# DCF77_transmitter2.net
KiCad netlist of a schematic drawn in EAGLE
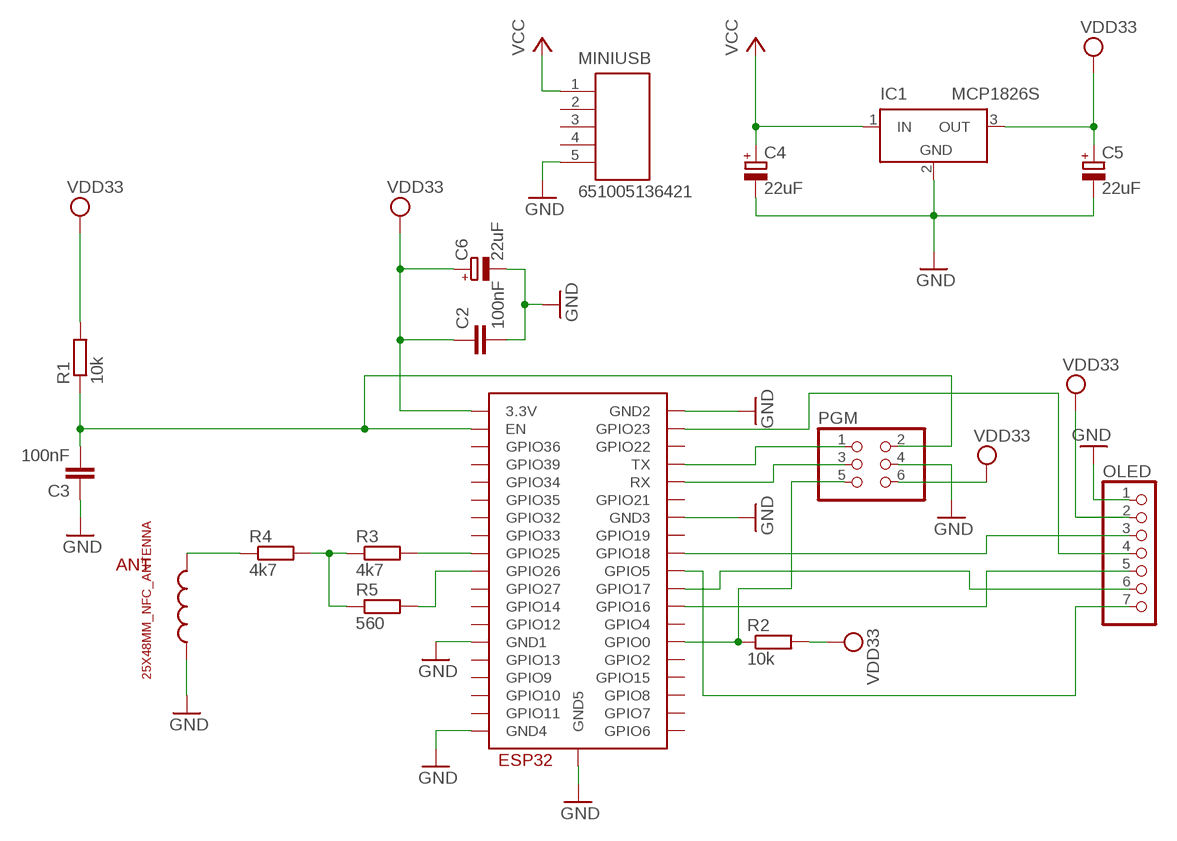
[diagram p0: schematic, sheet 1]

(export (version "E")
  (design (tool "Eeschema 10.0.6"))
  (components
    (comp (ref "ANT")
      (value "25X48MM_NFC_ANTENNA")
      (footprint "eagle-import:25X48MM_NFC_ANTENNA")
      (libsource (lib "eagle-import") (part "25X48MM_NFC_ANTENNA"))
    )
    (comp (ref "C2")
      (value "100nF")
      (footprint "eagle-import:C1206")
      (libsource (lib "eagle-import") (part "C-EUC1206"))
    )
    (comp (ref "C3")
      (value "100nF")
      (footprint "eagle-import:C1206")
      (libsource (lib "eagle-import") (part "C-EUC1206"))
    )
    (comp (ref "C4")
      (value "22uF")
      (footprint "eagle-import:B_3528-21W")
      (libsource (lib "eagle-import") (part "CPOL-EUB/3528-21W"))
    )
    (comp (ref "C5")
      (value "22uF")
      (footprint "eagle-import:B_3528-21W")
      (libsource (lib "eagle-import") (part "CPOL-EUB/3528-21W"))
    )
    (comp (ref "C6")
      (value "22uF")
      (footprint "eagle-import:B_3528-21W")
      (libsource (lib "eagle-import") (part "CPOL-EUB/3528-21W"))
    )
    (comp (ref "IC1")
      (value "MCP1826S")
      (footprint "eagle-import:SOT223")
      (fields (field (name "MPN") "LT1129CST-5#PBF"))
      (libsource (lib "eagle-import") (part "LT1129CST5"))
    )
    (comp (ref "MINIUSB")
      (value "651005136421")
      (footprint "eagle-import:651005136421")
      (libsource (lib "eagle-import") (part "651005136421"))
    )
    (comp (ref "OLED")
      (value "PINHD-1X7")
      (footprint "eagle-import:1X07")
      (libsource (lib "eagle-import") (part "PINHD-1X7"))
    )
    (comp (ref "PGM")
      (value "PINHD-2X3")
      (footprint "eagle-import:2X03")
      (libsource (lib "eagle-import") (part "PINHD-2X3"))
    )
    (comp (ref "R1")
      (value "10k")
      (footprint "eagle-import:R1206")
      (libsource (lib "eagle-import") (part "R-EU_R1206"))
    )
    (comp (ref "R2")
      (value "10k")
      (footprint "eagle-import:R1206")
      (libsource (lib "eagle-import") (part "R-EU_R1206"))
    )
    (comp (ref "R3")
      (value "4k7")
      (footprint "eagle-import:R1206")
      (libsource (lib "eagle-import") (part "R-EU_R1206"))
    )
    (comp (ref "R4")
      (value "4k7")
      (footprint "eagle-import:R1206")
      (libsource (lib "eagle-import") (part "R-EU_R1206"))
    )
    (comp (ref "R5")
      (value "560")
      (footprint "eagle-import:R1206")
      (libsource (lib "eagle-import") (part "R-EU_R1206"))
    )
    (comp (ref "U$2")
      (value "ESP32-WROOM")
      (footprint "eagle-import:ESP32-WROOM")
      (libsource (lib "eagle-import") (part "ESP32-WROOM"))
    )
  )
  (nets
    (net (code "1") (name "GND") (class "Default")
      (node (ref "ANT") (pin "P$2") (pinfunction "P$2_P$2") (pintype "bidirectional"))
      (node (ref "C2") (pin "2") (pinfunction "2_2") (pintype "passive"))
      (node (ref "C3") (pin "1") (pinfunction "1_1") (pintype "passive"))
      (node (ref "C4") (pin "-") (pinfunction "-_-") (pintype "passive"))
      (node (ref "C5") (pin "-") (pinfunction "-_-") (pintype "passive"))
      (node (ref "C6") (pin "-") (pinfunction "-_-") (pintype "passive"))
      (node (ref "IC1") (pin "2") (pinfunction "GND_2") (pintype "power_in"))
      (node (ref "MINIUSB") (pin "5") (pinfunction "5_5") (pintype "passive"))
      (node (ref "OLED") (pin "1") (pinfunction "1_1") (pintype "passive"))
      (node (ref "PGM") (pin "4") (pinfunction "4_4") (pintype "passive"))
      (node (ref "U$2") (pin "GND1") (pinfunction "GND1_GND1") (pintype "bidirectional"))
      (node (ref "U$2") (pin "GND2") (pinfunction "GND2_GND2") (pintype "bidirectional"))
      (node (ref "U$2") (pin "GND3") (pinfunction "GND3_GND3") (pintype "bidirectional"))
      (node (ref "U$2") (pin "GND4") (pinfunction "GND4_GND4") (pintype "bidirectional"))
      (node (ref "U$2") (pin "GND5") (pinfunction "GND5_GND5") (pintype "bidirectional"))
    )
    (net (code "2") (name "Net-(ANT-PadP$1)") (class "Default")
      (node (ref "ANT") (pin "P$1") (pinfunction "P$1_P$1") (pintype "bidirectional"))
      (node (ref "R4") (pin "1") (pinfunction "1_1") (pintype "passive"))
    )
    (net (code "3") (name "Net-(C3-Pad2)") (class "Default")
      (node (ref "C3") (pin "2") (pinfunction "2_2") (pintype "passive"))
      (node (ref "PGM") (pin "2") (pinfunction "2_2") (pintype "passive"))
      (node (ref "R1") (pin "1") (pinfunction "1_1") (pintype "passive"))
      (node (ref "U$2") (pin "EN") (pinfunction "EN_EN") (pintype "bidirectional"))
    )
    (net (code "4") (name "Net-(PGM-Pad1)") (class "Default")
      (node (ref "PGM") (pin "1") (pinfunction "1_1") (pintype "passive"))
      (node (ref "U$2") (pin "TX") (pinfunction "TX_TX") (pintype "bidirectional"))
    )
    (net (code "5") (name "Net-(PGM-Pad3)") (class "Default")
      (node (ref "PGM") (pin "3") (pinfunction "3_3") (pintype "passive"))
      (node (ref "U$2") (pin "RX") (pinfunction "RX_RX") (pintype "bidirectional"))
    )
    (net (code "6") (name "Net-(R3-Pad1)") (class "Default")
      (node (ref "R3") (pin "1") (pinfunction "1_1") (pintype "passive"))
      (node (ref "R4") (pin "2") (pinfunction "2_2") (pintype "passive"))
      (node (ref "R5") (pin "1") (pinfunction "1_1") (pintype "passive"))
    )
    (net (code "7") (name "Net-(U$2-GPIO0)") (class "Default")
      (node (ref "PGM") (pin "5") (pinfunction "5_5") (pintype "passive"))
      (node (ref "R2") (pin "1") (pinfunction "1_1") (pintype "passive"))
      (node (ref "U$2") (pin "IO0") (pinfunction "GPIO0_IO0") (pintype "bidirectional"))
    )
    (net (code "8") (name "Net-(U$2-GPIO5)") (class "Default")
      (node (ref "OLED") (pin "7") (pinfunction "7_7") (pintype "passive"))
      (node (ref "U$2") (pin "IO5") (pinfunction "GPIO5_IO5") (pintype "bidirectional"))
    )
    (net (code "9") (name "Net-(U$2-GPIO16)") (class "Default")
      (node (ref "OLED") (pin "5") (pinfunction "5_5") (pintype "passive"))
      (node (ref "U$2") (pin "IO16") (pinfunction "GPIO16_IO16") (pintype "bidirectional"))
    )
    (net (code "10") (name "Net-(U$2-GPIO17)") (class "Default")
      (node (ref "OLED") (pin "6") (pinfunction "6_6") (pintype "passive"))
      (node (ref "U$2") (pin "IO17") (pinfunction "GPIO17_IO17") (pintype "bidirectional"))
    )
    (net (code "11") (name "Net-(U$2-GPIO18)") (class "Default")
      (node (ref "OLED") (pin "3") (pinfunction "3_3") (pintype "passive"))
      (node (ref "U$2") (pin "IO18") (pinfunction "GPIO18_IO18") (pintype "bidirectional"))
    )
    (net (code "12") (name "Net-(U$2-GPIO23)") (class "Default")
      (node (ref "OLED") (pin "4") (pinfunction "4_4") (pintype "passive"))
      (node (ref "U$2") (pin "IO23") (pinfunction "GPIO23_IO23") (pintype "bidirectional"))
    )
    (net (code "13") (name "Net-(U$2-GPIO25)") (class "Default")
      (node (ref "R3") (pin "2") (pinfunction "2_2") (pintype "passive"))
      (node (ref "U$2") (pin "IO25") (pinfunction "GPIO25_IO25") (pintype "bidirectional"))
    )
    (net (code "14") (name "Net-(U$2-GPIO26)") (class "Default")
      (node (ref "R5") (pin "2") (pinfunction "2_2") (pintype "passive"))
      (node (ref "U$2") (pin "IO26") (pinfunction "GPIO26_IO26") (pintype "bidirectional"))
    )
    (net (code "15") (name "VCC") (class "Default")
      (node (ref "C4") (pin "+") (pinfunction "+_+") (pintype "passive"))
      (node (ref "IC1") (pin "1") (pinfunction "IN_1") (pintype "input"))
      (node (ref "MINIUSB") (pin "1") (pinfunction "1_1") (pintype "passive"))
    )
    (net (code "16") (name "VDD33") (class "Default")
      (node (ref "C2") (pin "1") (pinfunction "1_1") (pintype "passive"))
      (node (ref "C5") (pin "+") (pinfunction "+_+") (pintype "passive"))
      (node (ref "C6") (pin "+") (pinfunction "+_+") (pintype "passive"))
      (node (ref "IC1") (pin "3") (pinfunction "OUT_3") (pintype "output"))
      (node (ref "OLED") (pin "2") (pinfunction "2_2") (pintype "passive"))
      (node (ref "PGM") (pin "6") (pinfunction "6_6") (pintype "passive"))
      (node (ref "R1") (pin "2") (pinfunction "2_2") (pintype "passive"))
      (node (ref "R2") (pin "2") (pinfunction "2_2") (pintype "passive"))
      (node (ref "U$2") (pin "3V3") (pinfunction "3.3V_3V3") (pintype "bidirectional"))
    )
    (net (code "17") (name "unconnected-(MINIUSB-Pad2)") (class "Default")
      (node (ref "MINIUSB") (pin "2") (pinfunction "2_2") (pintype "passive"))
    )
    (net (code "18") (name "unconnected-(MINIUSB-Pad3)") (class "Default")
      (node (ref "MINIUSB") (pin "3") (pinfunction "3_3") (pintype "passive"))
    )
    (net (code "19") (name "unconnected-(MINIUSB-Pad4)") (class "Default")
      (node (ref "MINIUSB") (pin "4") (pinfunction "4_4") (pintype "passive"))
    )
    (net (code "20") (name "unconnected-(U$2-GPIO2-PadIO2)") (class "Default")
      (node (ref "U$2") (pin "IO2") (pinfunction "GPIO2_IO2") (pintype "bidirectional"))
    )
    (net (code "21") (name "unconnected-(U$2-GPIO4-PadIO4)") (class "Default")
      (node (ref "U$2") (pin "IO4") (pinfunction "GPIO4_IO4") (pintype "bidirectional"))
    )
    (net (code "22") (name "unconnected-(U$2-GPIO6-PadCLK)") (class "Default")
      (node (ref "U$2") (pin "CLK") (pinfunction "GPIO6_CLK") (pintype "bidirectional"))
    )
    (net (code "23") (name "unconnected-(U$2-GPIO7-PadSD0)") (class "Default")
      (node (ref "U$2") (pin "SD0") (pinfunction "GPIO7_SD0") (pintype "bidirectional"))
    )
    (net (code "24") (name "unconnected-(U$2-GPIO8-PadSD1)") (class "Default")
      (node (ref "U$2") (pin "SD1") (pinfunction "GPIO8_SD1") (pintype "bidirectional"))
    )
    (net (code "25") (name "unconnected-(U$2-GPIO9-PadSD2)") (class "Default")
      (node (ref "U$2") (pin "SD2") (pinfunction "GPIO9_SD2") (pintype "bidirectional"))
    )
    (net (code "26") (name "unconnected-(U$2-GPIO10-PadSD3)") (class "Default")
      (node (ref "U$2") (pin "SD3") (pinfunction "GPIO10_SD3") (pintype "bidirectional"))
    )
    (net (code "27") (name "unconnected-(U$2-GPIO11-PadCMD)") (class "Default")
      (node (ref "U$2") (pin "CMD") (pinfunction "GPIO11_CMD") (pintype "bidirectional"))
    )
    (net (code "28") (name "unconnected-(U$2-GPIO12-PadIO12)") (class "Default")
      (node (ref "U$2") (pin "IO12") (pinfunction "GPIO12_IO12") (pintype "bidirectional"))
    )
    (net (code "29") (name "unconnected-(U$2-GPIO13-PadIO13)") (class "Default")
      (node (ref "U$2") (pin "IO13") (pinfunction "GPIO13_IO13") (pintype "bidirectional"))
    )
    (net (code "30") (name "unconnected-(U$2-GPIO14-PadIO14)") (class "Default")
      (node (ref "U$2") (pin "IO14") (pinfunction "GPIO14_IO14") (pintype "bidirectional"))
    )
    (net (code "31") (name "unconnected-(U$2-GPIO15-PadIO15)") (class "Default")
      (node (ref "U$2") (pin "IO15") (pinfunction "GPIO15_IO15") (pintype "bidirectional"))
    )
    (net (code "32") (name "unconnected-(U$2-GPIO19-PadIO19)") (class "Default")
      (node (ref "U$2") (pin "IO19") (pinfunction "GPIO19_IO19") (pintype "bidirectional"))
    )
    (net (code "33") (name "unconnected-(U$2-GPIO21-PadIO21)") (class "Default")
      (node (ref "U$2") (pin "IO21") (pinfunction "GPIO21_IO21") (pintype "bidirectional"))
    )
    (net (code "34") (name "unconnected-(U$2-GPIO22-PadIO22)") (class "Default")
      (node (ref "U$2") (pin "IO22") (pinfunction "GPIO22_IO22") (pintype "bidirectional"))
    )
    (net (code "35") (name "unconnected-(U$2-GPIO27-PadIO27)") (class "Default")
      (node (ref "U$2") (pin "IO27") (pinfunction "GPIO27_IO27") (pintype "bidirectional"))
    )
    (net (code "36") (name "unconnected-(U$2-GPIO32-PadIO32)") (class "Default")
      (node (ref "U$2") (pin "IO32") (pinfunction "GPIO32_IO32") (pintype "bidirectional"))
    )
    (net (code "37") (name "unconnected-(U$2-GPIO33-PadIO33)") (class "Default")
      (node (ref "U$2") (pin "IO33") (pinfunction "GPIO33_IO33") (pintype "bidirectional"))
    )
    (net (code "38") (name "unconnected-(U$2-GPIO34-PadIO34)") (class "Default")
      (node (ref "U$2") (pin "IO34") (pinfunction "GPIO34_IO34") (pintype "bidirectional"))
    )
    (net (code "39") (name "unconnected-(U$2-GPIO35-PadIO35)") (class "Default")
      (node (ref "U$2") (pin "IO35") (pinfunction "GPIO35_IO35") (pintype "bidirectional"))
    )
    (net (code "40") (name "unconnected-(U$2-GPIO36-PadSENSOR_VP)") (class "Default")
      (node (ref "U$2") (pin "SENSOR_VP") (pinfunction "GPIO36_SENSOR_VP") (pintype "bidirectional"))
    )
    (net (code "41") (name "unconnected-(U$2-GPIO39-PadSENSOR_VN)") (class "Default")
      (node (ref "U$2") (pin "SENSOR_VN") (pinfunction "GPIO39_SENSOR_VN") (pintype "bidirectional"))
    )
  )
)
